# IO_Peripherals.net
KiCad netlist of a schematic drawn in Altium Designer
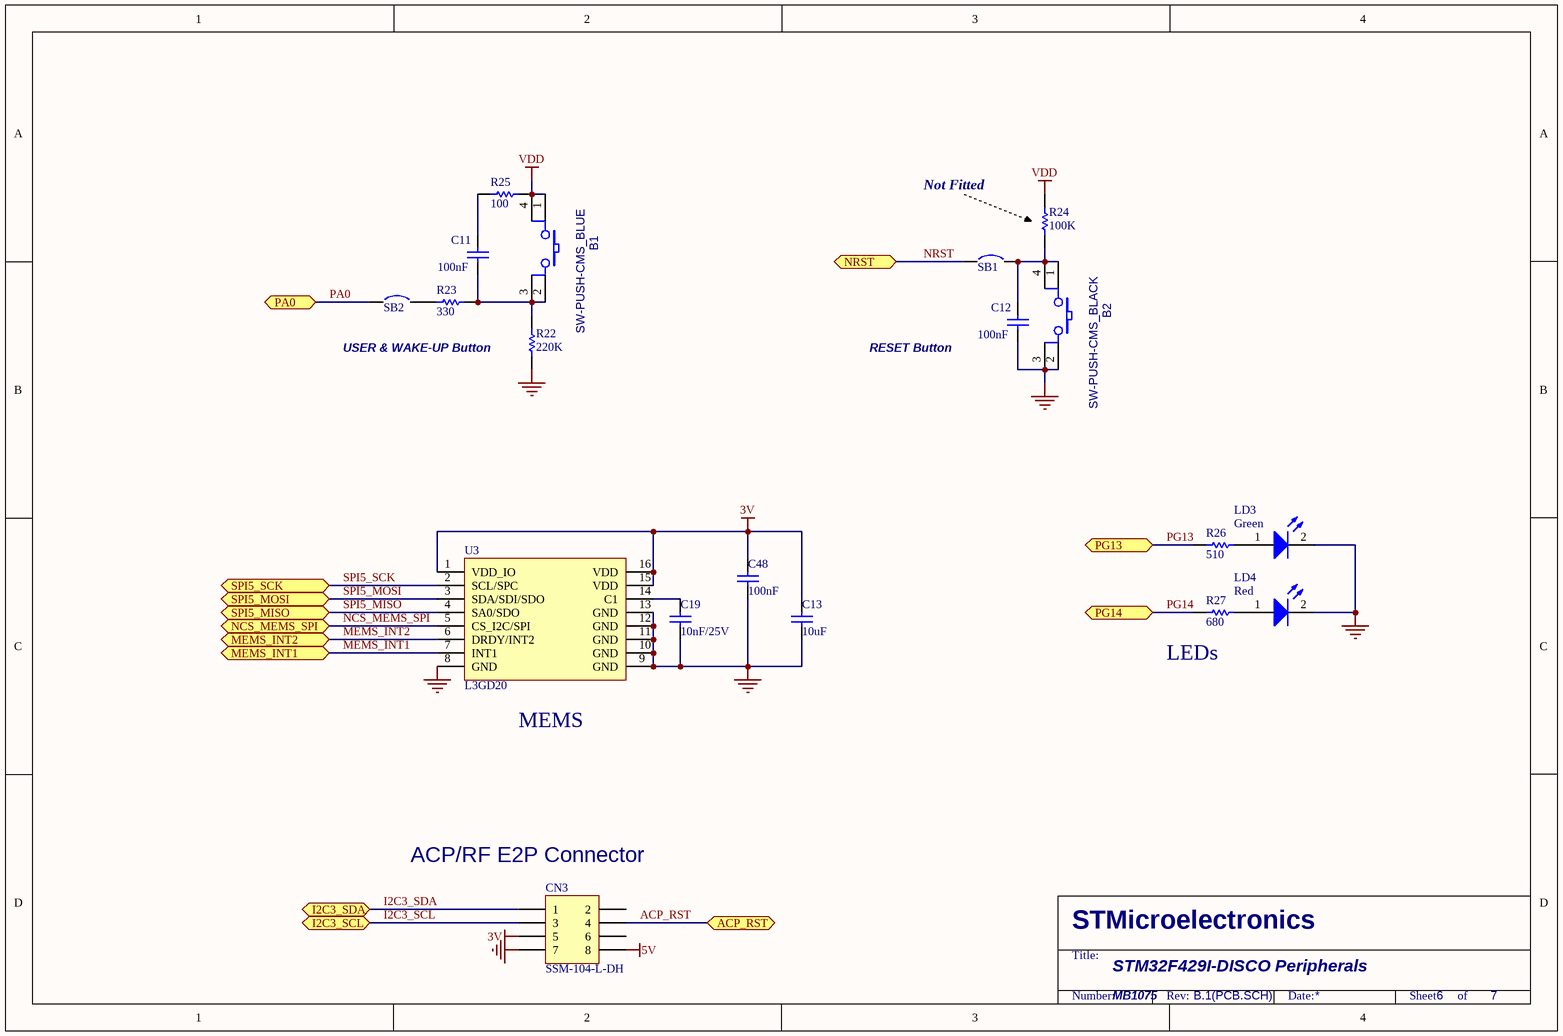
[diagram p0: IO Peripherals.SchDoc]

(export (version "E")
  (design (tool "Eeschema 10.0.6"))
  (components
    (comp (ref "B1")
      (value "SW-PUSH-CMS_BLUE")
      (footprint "STM-SMEE:BP1CMS")
      (description "Non-Open Push Button,Blue 0.1A 24V,Square head,6*6,SMT,180Degree,TD-0341X-GO1,wealthmetal")
      (libsource (lib "MCD_TOOLS") (part "SW-PUSH-CMS_BLUE"))
    )
    (comp (ref "B2")
      (value "SW-PUSH-CMS_BLACK")
      (footprint "STM-SMEE:BP1CMS")
      (description "Non-Open Push Button,Black 0.1A 24V,Square head,6*6,SMT,180Degree,TD-0341X-GO1,wealthmetal")
      (libsource (lib "MCD_TOOLS") (part "SW-PUSH-CMS_BLACK"))
    )
    (comp (ref "C11")
      (value "100nF")
      (footprint "0402C")
      (description "Capacitor 0402 / 0603 / 0805")
      (libsource (lib "MCD_TOOLS") (part "Capacitor_ST"))
    )
    (comp (ref "C12")
      (value "100nF")
      (footprint "0402C")
      (description "Capacitor 0402 / 0603 / 0805")
      (libsource (lib "MCD_TOOLS") (part "Capacitor_ST"))
    )
    (comp (ref "C13")
      (value "10uF")
      (footprint "0603C")
      (description "Capacitor")
      (fields (field (name "PUBLISHER") "Altium Limited"))
      (libsource (lib "Miscellaneous Devices") (part "CAP"))
    )
    (comp (ref "C19")
      (value "10nF/25V")
      (footprint "0603C")
      (description "Capacitor")
      (fields (field (name "PUBLISHER") "Altium Limited"))
      (libsource (lib "Miscellaneous Devices") (part "CAP"))
    )
    (comp (ref "C48")
      (value "100nF")
      (footprint "0402C")
      (description "Capacitor 0402 / 0603 / 0805")
      (libsource (lib "MCD_TOOLS") (part "Capacitor_ST"))
    )
    (comp (ref "CN3")
      (value "SSM-104-L-DH")
      (footprint "SSM-104-L-DH")
      (description "Header, 5-Pin, Dual row")
      (fields (field (name "PUBLISHER") "Altium Limited"))
      (libsource (lib "mb1045") (part "SSM-104-L-DH"))
    )
    (comp (ref "LD3")
      (value "Green")
      (footprint "0603D")
      (description "Typical RED, GREEN, YELLOW, AMBER GaAs LED")
      (fields (field (name "PUBLISHER") "Altium Limited"))
      (libsource (lib "Miscellaneous Devices") (part "LED2"))
    )
    (comp (ref "LD4")
      (value "Red")
      (footprint "0603D")
      (description "Typical RED, GREEN, YELLOW, AMBER GaAs LED")
      (fields (field (name "PUBLISHER") "Altium Limited"))
      (libsource (lib "Miscellaneous Devices") (part "LED2"))
    )
    (comp (ref "R22")
      (value "220K")
      (footprint "0402R")
      (description "Resistor 0402 or 0603 or 0805")
      (libsource (lib "MCD_TOOLS") (part "Resistor_ST"))
    )
    (comp (ref "R23")
      (value "330")
      (footprint "0402R")
      (description "Resistor 0402 or 0603 or 0805")
      (libsource (lib "MCD_TOOLS") (part "Resistor_ST"))
    )
    (comp (ref "R24")
      (value "100K")
      (footprint "0402R")
      (description "Resistor 0402 or 0603 or 0805")
      (libsource (lib "MCD_TOOLS") (part "Resistor_ST"))
    )
    (comp (ref "R25")
      (value "100")
      (footprint "0402R")
      (description "Resistor 0402 or 0603 or 0805")
      (libsource (lib "MCD_TOOLS") (part "Resistor_ST"))
    )
    (comp (ref "R26")
      (value "510")
      (footprint "0603R")
      (description "Resistor 0402 or 0603 or 0805")
      (libsource (lib "MCD_TOOLS") (part "Resistor_ST"))
    )
    (comp (ref "R27")
      (value "680")
      (footprint "0603R")
      (description "Resistor 0402 or 0603 or 0805")
      (libsource (lib "MCD_TOOLS") (part "Resistor_ST"))
    )
    (comp (ref "SB1")
      (value "Circuit Breaker")
      (footprint "JP2_SMD")
      (fields (field (name "PUBLISHER") "Altium Limited"))
      (libsource (lib "MB915") (part "Circuit Breaker"))
    )
    (comp (ref "SB2")
      (value "Circuit Breaker")
      (footprint "JP2_SMD")
      (fields (field (name "PUBLISHER") "Altium Limited"))
      (libsource (lib "MB915") (part "Circuit Breaker"))
    )
    (comp (ref "U3")
      (value "L3GD20")
      (footprint "STM-SMEE:LGA16-4x4")
      (description "MEMS motion sensor three-axis digital output gyroscopeelerometer")
      (libsource (lib "MCD_TOOLS") (part "L3GD20"))
    )
  )
  (nets
    (net (code "1") (name "/ACP_RST") (class "Default")
      (node (ref "CN3") (pin "4") (pinfunction "4_4") (pintype "passive"))
    )
    (net (code "2") (name "/I2C3_SCL") (class "Default")
      (node (ref "CN3") (pin "3") (pinfunction "3_3") (pintype "passive"))
    )
    (net (code "3") (name "/I2C3_SDA") (class "Default")
      (node (ref "CN3") (pin "1") (pinfunction "1_1") (pintype "passive"))
    )
    (net (code "4") (name "/MEMS_INT1") (class "Default")
      (node (ref "U3") (pin "7") (pinfunction "INT1_7") (pintype "passive"))
    )
    (net (code "5") (name "/MEMS_INT2") (class "Default")
      (node (ref "U3") (pin "6") (pinfunction "DRDY/INT2_6") (pintype "passive"))
    )
    (net (code "6") (name "/NCS_MEMS_SPI") (class "Default")
      (node (ref "U3") (pin "5") (pinfunction "CS_I2C/SPI_5") (pintype "passive"))
    )
    (net (code "7") (name "/NRST") (class "Default")
      (node (ref "SB1") (pin "1") (pinfunction "1_1") (pintype "passive"))
    )
    (net (code "8") (name "/PA0") (class "Default")
      (node (ref "SB2") (pin "1") (pinfunction "1_1") (pintype "passive"))
    )
    (net (code "9") (name "/PG13") (class "Default")
      (node (ref "R26") (pin "1") (pinfunction "1_1") (pintype "passive"))
    )
    (net (code "10") (name "/PG14") (class "Default")
      (node (ref "R27") (pin "1") (pinfunction "1_1") (pintype "passive"))
    )
    (net (code "11") (name "/SPI5_MISO") (class "Default")
      (node (ref "U3") (pin "4") (pinfunction "SA0/SDO_4") (pintype "passive"))
    )
    (net (code "12") (name "/SPI5_MOSI") (class "Default")
      (node (ref "U3") (pin "3") (pinfunction "SDA/SDI/SDO_3") (pintype "passive"))
    )
    (net (code "13") (name "/SPI5_SCK") (class "Default")
      (node (ref "U3") (pin "2") (pinfunction "SCL/SPC_2") (pintype "passive"))
    )
    (net (code "14") (name "3V") (class "Default")
      (node (ref "C13") (pin "2") (pinfunction "2_2") (pintype "passive"))
      (node (ref "C48") (pin "2") (pinfunction "2_2") (pintype "passive"))
      (node (ref "CN3") (pin "5") (pinfunction "5_5") (pintype "passive"))
      (node (ref "U3") (pin "1") (pinfunction "VDD_IO_1") (pintype "passive"))
      (node (ref "U3") (pin "15") (pinfunction "VDD_15") (pintype "passive"))
      (node (ref "U3") (pin "16") (pinfunction "VDD_16") (pintype "passive"))
    )
    (net (code "15") (name "5V") (class "Default")
      (node (ref "CN3") (pin "8") (pinfunction "8_8") (pintype "passive"))
    )
    (net (code "16") (name "GND") (class "Default")
      (node (ref "B2") (pin "2") (pinfunction "2_2") (pintype "passive"))
      (node (ref "B2") (pin "3") (pinfunction "3_3") (pintype "passive"))
      (node (ref "C12") (pin "1") (pinfunction "1_1") (pintype "passive"))
      (node (ref "C13") (pin "1") (pinfunction "1_1") (pintype "passive"))
      (node (ref "C19") (pin "1") (pinfunction "1_1") (pintype "passive"))
      (node (ref "C48") (pin "1") (pinfunction "1_1") (pintype "passive"))
      (node (ref "CN3") (pin "7") (pinfunction "7_7") (pintype "passive"))
      (node (ref "LD3") (pin "2") (pinfunction "K_2") (pintype "passive"))
      (node (ref "LD4") (pin "2") (pinfunction "K_2") (pintype "passive"))
      (node (ref "R22") (pin "1") (pinfunction "1_1") (pintype "passive"))
      (node (ref "U3") (pin "10") (pinfunction "GND_10") (pintype "passive"))
      (node (ref "U3") (pin "11") (pinfunction "GND_11") (pintype "passive"))
      (node (ref "U3") (pin "12") (pinfunction "GND_12") (pintype "passive"))
      (node (ref "U3") (pin "13") (pinfunction "GND_13") (pintype "passive"))
      (node (ref "U3") (pin "8") (pinfunction "GND_8") (pintype "passive"))
      (node (ref "U3") (pin "9") (pinfunction "GND_9") (pintype "passive"))
    )
    (net (code "17") (name "Net-(B1-Pad2)") (class "Default")
      (node (ref "B1") (pin "2") (pinfunction "2_2") (pintype "passive"))
      (node (ref "B1") (pin "3") (pinfunction "3_3") (pintype "passive"))
      (node (ref "C11") (pin "1") (pinfunction "1_1") (pintype "passive"))
      (node (ref "R22") (pin "2") (pinfunction "2_2") (pintype "passive"))
      (node (ref "R23") (pin "2") (pinfunction "2_2") (pintype "passive"))
    )
    (net (code "18") (name "Net-(B2-Pad1)") (class "Default")
      (node (ref "B2") (pin "1") (pinfunction "1_1") (pintype "passive"))
      (node (ref "B2") (pin "4") (pinfunction "4_4") (pintype "passive"))
      (node (ref "C12") (pin "2") (pinfunction "2_2") (pintype "passive"))
      (node (ref "R24") (pin "1") (pinfunction "1_1") (pintype "passive"))
      (node (ref "SB1") (pin "2") (pinfunction "2_2") (pintype "passive"))
    )
    (net (code "19") (name "Net-(C11-Pad2)") (class "Default")
      (node (ref "C11") (pin "2") (pinfunction "2_2") (pintype "passive"))
      (node (ref "R25") (pin "1") (pinfunction "1_1") (pintype "passive"))
    )
    (net (code "20") (name "Net-(LD3-A)") (class "Default")
      (node (ref "LD3") (pin "1") (pinfunction "A_1") (pintype "passive"))
      (node (ref "R26") (pin "2") (pinfunction "2_2") (pintype "passive"))
    )
    (net (code "21") (name "Net-(LD4-A)") (class "Default")
      (node (ref "LD4") (pin "1") (pinfunction "A_1") (pintype "passive"))
      (node (ref "R27") (pin "2") (pinfunction "2_2") (pintype "passive"))
    )
    (net (code "22") (name "Net-(R23-Pad1)") (class "Default")
      (node (ref "R23") (pin "1") (pinfunction "1_1") (pintype "passive"))
      (node (ref "SB2") (pin "2") (pinfunction "2_2") (pintype "passive"))
    )
    (net (code "23") (name "Net-(U3-C1)") (class "Default")
      (node (ref "C19") (pin "2") (pinfunction "2_2") (pintype "passive"))
      (node (ref "U3") (pin "14") (pinfunction "C1_14") (pintype "passive"))
    )
    (net (code "24") (name "VDD") (class "Default")
      (node (ref "B1") (pin "1") (pinfunction "1_1") (pintype "passive"))
      (node (ref "B1") (pin "4") (pinfunction "4_4") (pintype "passive"))
      (node (ref "R24") (pin "2") (pinfunction "2_2") (pintype "passive"))
      (node (ref "R25") (pin "2") (pinfunction "2_2") (pintype "passive"))
    )
    (net (code "25") (name "unconnected-(CN3-Pad2)") (class "Default")
      (node (ref "CN3") (pin "2") (pinfunction "2_2") (pintype "passive"))
    )
    (net (code "26") (name "unconnected-(CN3-Pad6)") (class "Default")
      (node (ref "CN3") (pin "6") (pinfunction "6_6") (pintype "passive"))
    )
  )
)
